# keybaord60.net
KiCad netlist of a schematic drawn in EAGLE
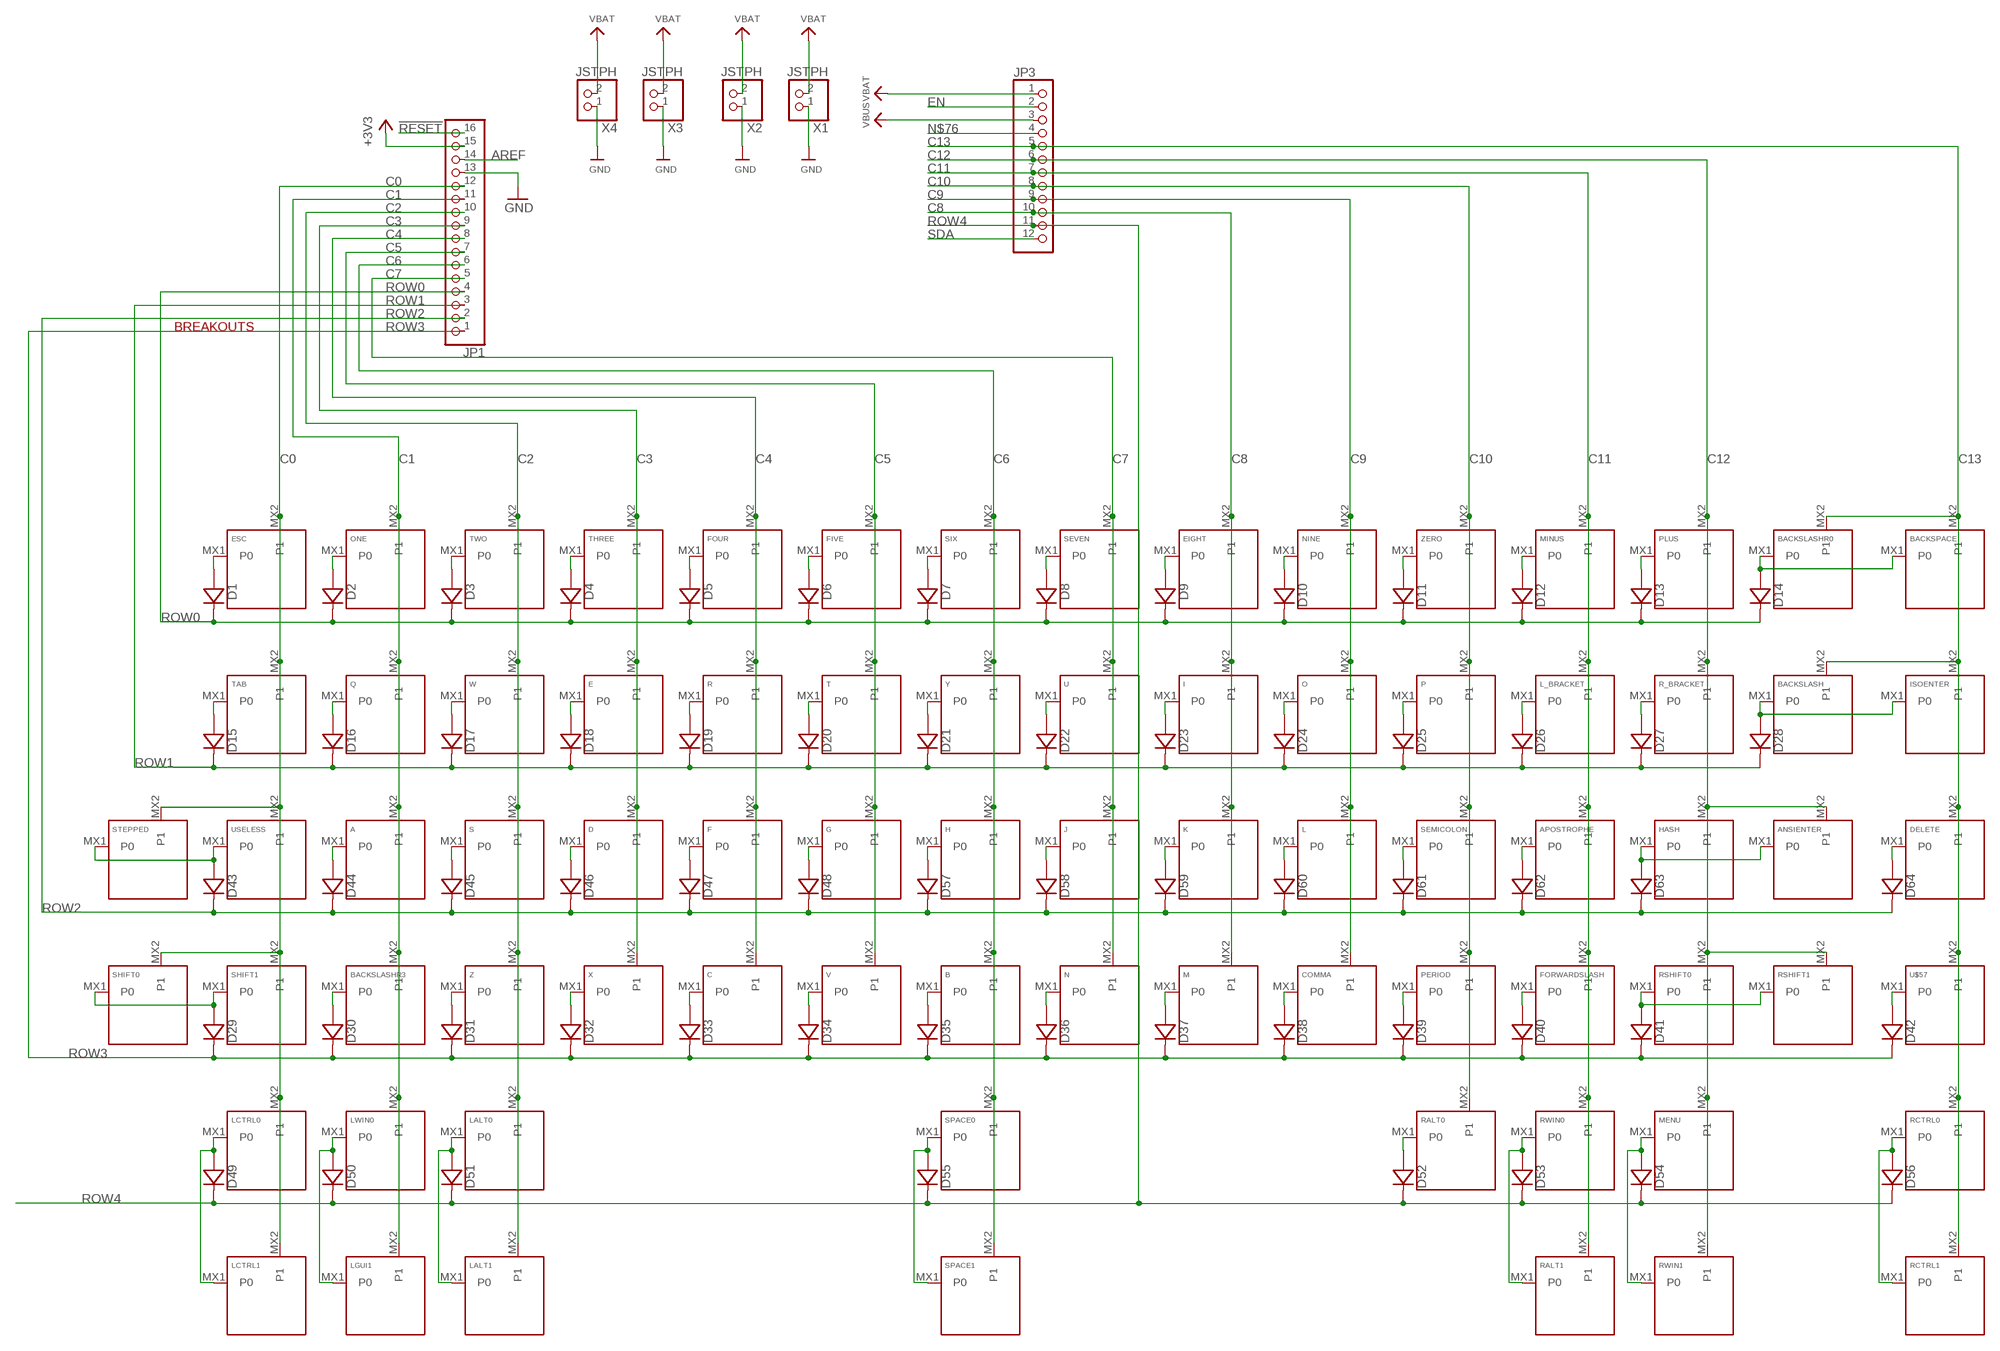
[diagram p0: schematic, sheet 1]

(export (version "E")
  (design (tool "Eeschema 10.0.6"))
  (components
    (comp (ref "A")
      (value "KEYSWITCH-PLAIN-MX-1U")
      (footprint "eagle-import:MX-1U")
      (libsource (lib "eagle-import") (part "KEYSWITCH-PLAIN-MX-1U"))
    )
    (comp (ref "ANSIENTER")
      (value "KEYSWITCH-PLAIN-MX-2U")
      (footprint "eagle-import:MX-2U")
      (libsource (lib "eagle-import") (part "KEYSWITCH-PLAIN-MX-2U"))
    )
    (comp (ref "APOSTROPHE")
      (value "KEYSWITCH-PLAIN-MX-1U")
      (footprint "eagle-import:MX-1U")
      (libsource (lib "eagle-import") (part "KEYSWITCH-PLAIN-MX-1U"))
    )
    (comp (ref "B")
      (value "KEYSWITCH-PLAIN-MX-1U")
      (footprint "eagle-import:MX-1U")
      (libsource (lib "eagle-import") (part "KEYSWITCH-PLAIN-MX-1U"))
    )
    (comp (ref "BACKSLASH")
      (value "KEYSWITCH-PLAIN-MX-1U")
      (footprint "eagle-import:MX-1U")
      (libsource (lib "eagle-import") (part "KEYSWITCH-PLAIN-MX-1U"))
    )
    (comp (ref "BACKSLASHR0")
      (value "KEYSWITCH-PLAIN-MX-1U")
      (footprint "eagle-import:MX-1U")
      (libsource (lib "eagle-import") (part "KEYSWITCH-PLAIN-MX-1U"))
    )
    (comp (ref "BACKSLASHR3")
      (value "KEYSWITCH-PLAIN-MX-1U")
      (footprint "eagle-import:MX-1U")
      (libsource (lib "eagle-import") (part "KEYSWITCH-PLAIN-MX-1U"))
    )
    (comp (ref "BACKSPACE")
      (value "KEYSWITCH-PLAIN-MX-2U")
      (footprint "eagle-import:MX-2U")
      (libsource (lib "eagle-import") (part "KEYSWITCH-PLAIN-MX-2U"))
    )
    (comp (ref "C")
      (value "KEYSWITCH-PLAIN-MX-1U")
      (footprint "eagle-import:MX-1U")
      (libsource (lib "eagle-import") (part "KEYSWITCH-PLAIN-MX-1U"))
    )
    (comp (ref "COMMA")
      (value "KEYSWITCH-PLAIN-MX-1U")
      (footprint "eagle-import:MX-1U")
      (libsource (lib "eagle-import") (part "KEYSWITCH-PLAIN-MX-1U"))
    )
    (comp (ref "D")
      (value "KEYSWITCH-PLAIN-MX-1U")
      (footprint "eagle-import:MX-1U")
      (libsource (lib "eagle-import") (part "KEYSWITCH-PLAIN-MX-1U"))
    )
    (comp (ref "D1")
      (value "DIODE-SOD-123")
      (footprint "eagle-import:SOD-123")
      (libsource (lib "eagle-import") (part "DIODE-SOD-123"))
    )
    (comp (ref "D2")
      (value "DIODE-SOD-123")
      (footprint "eagle-import:SOD-123")
      (libsource (lib "eagle-import") (part "DIODE-SOD-123"))
    )
    (comp (ref "D3")
      (value "DIODE-SOD-123")
      (footprint "eagle-import:SOD-123")
      (libsource (lib "eagle-import") (part "DIODE-SOD-123"))
    )
    (comp (ref "D4")
      (value "DIODE-SOD-123")
      (footprint "eagle-import:SOD-123")
      (libsource (lib "eagle-import") (part "DIODE-SOD-123"))
    )
    (comp (ref "D5")
      (value "DIODE-SOD-123")
      (footprint "eagle-import:SOD-123")
      (libsource (lib "eagle-import") (part "DIODE-SOD-123"))
    )
    (comp (ref "D6")
      (value "DIODE-SOD-123")
      (footprint "eagle-import:SOD-123")
      (libsource (lib "eagle-import") (part "DIODE-SOD-123"))
    )
    (comp (ref "D7")
      (value "DIODE-SOD-123")
      (footprint "eagle-import:SOD-123")
      (libsource (lib "eagle-import") (part "DIODE-SOD-123"))
    )
    (comp (ref "D8")
      (value "DIODE-SOD-123")
      (footprint "eagle-import:SOD-123")
      (libsource (lib "eagle-import") (part "DIODE-SOD-123"))
    )
    (comp (ref "D9")
      (value "DIODE-SOD-123")
      (footprint "eagle-import:SOD-123")
      (libsource (lib "eagle-import") (part "DIODE-SOD-123"))
    )
    (comp (ref "D10")
      (value "DIODE-SOD-123")
      (footprint "eagle-import:SOD-123")
      (libsource (lib "eagle-import") (part "DIODE-SOD-123"))
    )
    (comp (ref "D11")
      (value "DIODE-SOD-123")
      (footprint "eagle-import:SOD-123")
      (libsource (lib "eagle-import") (part "DIODE-SOD-123"))
    )
    (comp (ref "D12")
      (value "DIODE-SOD-123")
      (footprint "eagle-import:SOD-123")
      (libsource (lib "eagle-import") (part "DIODE-SOD-123"))
    )
    (comp (ref "D13")
      (value "DIODE-SOD-123")
      (footprint "eagle-import:SOD-123")
      (libsource (lib "eagle-import") (part "DIODE-SOD-123"))
    )
    (comp (ref "D14")
      (value "DIODE-SOD-123")
      (footprint "eagle-import:SOD-123")
      (libsource (lib "eagle-import") (part "DIODE-SOD-123"))
    )
    (comp (ref "D15")
      (value "DIODE-SOD-123")
      (footprint "eagle-import:SOD-123")
      (libsource (lib "eagle-import") (part "DIODE-SOD-123"))
    )
    (comp (ref "D16")
      (value "DIODE-SOD-123")
      (footprint "eagle-import:SOD-123")
      (libsource (lib "eagle-import") (part "DIODE-SOD-123"))
    )
    (comp (ref "D17")
      (value "DIODE-SOD-123")
      (footprint "eagle-import:SOD-123")
      (libsource (lib "eagle-import") (part "DIODE-SOD-123"))
    )
    (comp (ref "D18")
      (value "DIODE-SOD-123")
      (footprint "eagle-import:SOD-123")
      (libsource (lib "eagle-import") (part "DIODE-SOD-123"))
    )
    (comp (ref "D19")
      (value "DIODE-SOD-123")
      (footprint "eagle-import:SOD-123")
      (libsource (lib "eagle-import") (part "DIODE-SOD-123"))
    )
    (comp (ref "D20")
      (value "DIODE-SOD-123")
      (footprint "eagle-import:SOD-123")
      (libsource (lib "eagle-import") (part "DIODE-SOD-123"))
    )
    (comp (ref "D21")
      (value "DIODE-SOD-123")
      (footprint "eagle-import:SOD-123")
      (libsource (lib "eagle-import") (part "DIODE-SOD-123"))
    )
    (comp (ref "D22")
      (value "DIODE-SOD-123")
      (footprint "eagle-import:SOD-123")
      (libsource (lib "eagle-import") (part "DIODE-SOD-123"))
    )
    (comp (ref "D23")
      (value "DIODE-SOD-123")
      (footprint "eagle-import:SOD-123")
      (libsource (lib "eagle-import") (part "DIODE-SOD-123"))
    )
    (comp (ref "D24")
      (value "DIODE-SOD-123")
      (footprint "eagle-import:SOD-123")
      (libsource (lib "eagle-import") (part "DIODE-SOD-123"))
    )
    (comp (ref "D25")
      (value "DIODE-SOD-123")
      (footprint "eagle-import:SOD-123")
      (libsource (lib "eagle-import") (part "DIODE-SOD-123"))
    )
    (comp (ref "D26")
      (value "DIODE-SOD-123")
      (footprint "eagle-import:SOD-123")
      (libsource (lib "eagle-import") (part "DIODE-SOD-123"))
    )
    (comp (ref "D27")
      (value "DIODE-SOD-123")
      (footprint "eagle-import:SOD-123")
      (libsource (lib "eagle-import") (part "DIODE-SOD-123"))
    )
    (comp (ref "D28")
      (value "DIODE-SOD-123")
      (footprint "eagle-import:SOD-123")
      (libsource (lib "eagle-import") (part "DIODE-SOD-123"))
    )
    (comp (ref "D29")
      (value "DIODE-SOD-123")
      (footprint "eagle-import:SOD-123")
      (libsource (lib "eagle-import") (part "DIODE-SOD-123"))
    )
    (comp (ref "D30")
      (value "DIODE-SOD-123")
      (footprint "eagle-import:SOD-123")
      (libsource (lib "eagle-import") (part "DIODE-SOD-123"))
    )
    (comp (ref "D31")
      (value "DIODE-SOD-123")
      (footprint "eagle-import:SOD-123")
      (libsource (lib "eagle-import") (part "DIODE-SOD-123"))
    )
    (comp (ref "D32")
      (value "DIODE-SOD-123")
      (footprint "eagle-import:SOD-123")
      (libsource (lib "eagle-import") (part "DIODE-SOD-123"))
    )
    (comp (ref "D33")
      (value "DIODE-SOD-123")
      (footprint "eagle-import:SOD-123")
      (libsource (lib "eagle-import") (part "DIODE-SOD-123"))
    )
    (comp (ref "D34")
      (value "DIODE-SOD-123")
      (footprint "eagle-import:SOD-123")
      (libsource (lib "eagle-import") (part "DIODE-SOD-123"))
    )
    (comp (ref "D35")
      (value "DIODE-SOD-123")
      (footprint "eagle-import:SOD-123")
      (libsource (lib "eagle-import") (part "DIODE-SOD-123"))
    )
    (comp (ref "D36")
      (value "DIODE-SOD-123")
      (footprint "eagle-import:SOD-123")
      (libsource (lib "eagle-import") (part "DIODE-SOD-123"))
    )
    (comp (ref "D37")
      (value "DIODE-SOD-123")
      (footprint "eagle-import:SOD-123")
      (libsource (lib "eagle-import") (part "DIODE-SOD-123"))
    )
    (comp (ref "D38")
      (value "DIODE-SOD-123")
      (footprint "eagle-import:SOD-123")
      (libsource (lib "eagle-import") (part "DIODE-SOD-123"))
    )
    (comp (ref "D39")
      (value "DIODE-SOD-123")
      (footprint "eagle-import:SOD-123")
      (libsource (lib "eagle-import") (part "DIODE-SOD-123"))
    )
    (comp (ref "D40")
      (value "DIODE-SOD-123")
      (footprint "eagle-import:SOD-123")
      (libsource (lib "eagle-import") (part "DIODE-SOD-123"))
    )
    (comp (ref "D41")
      (value "DIODE-SOD-123")
      (footprint "eagle-import:SOD-123")
      (libsource (lib "eagle-import") (part "DIODE-SOD-123"))
    )
    (comp (ref "D42")
      (value "DIODE-SOD-123")
      (footprint "eagle-import:SOD-123")
      (libsource (lib "eagle-import") (part "DIODE-SOD-123"))
    )
    (comp (ref "D43")
      (value "DIODE-SOD-123")
      (footprint "eagle-import:SOD-123")
      (libsource (lib "eagle-import") (part "DIODE-SOD-123"))
    )
    (comp (ref "D44")
      (value "DIODE-SOD-123")
      (footprint "eagle-import:SOD-123")
      (libsource (lib "eagle-import") (part "DIODE-SOD-123"))
    )
    (comp (ref "D45")
      (value "DIODE-SOD-123")
      (footprint "eagle-import:SOD-123")
      (libsource (lib "eagle-import") (part "DIODE-SOD-123"))
    )
    (comp (ref "D46")
      (value "DIODE-SOD-123")
      (footprint "eagle-import:SOD-123")
      (libsource (lib "eagle-import") (part "DIODE-SOD-123"))
    )
    (comp (ref "D47")
      (value "DIODE-SOD-123")
      (footprint "eagle-import:SOD-123")
      (libsource (lib "eagle-import") (part "DIODE-SOD-123"))
    )
    (comp (ref "D48")
      (value "DIODE-SOD-123")
      (footprint "eagle-import:SOD-123")
      (libsource (lib "eagle-import") (part "DIODE-SOD-123"))
    )
    (comp (ref "D49")
      (value "DIODE-SOD-123")
      (footprint "eagle-import:SOD-123")
      (libsource (lib "eagle-import") (part "DIODE-SOD-123"))
    )
    (comp (ref "D50")
      (value "DIODE-SOD-123")
      (footprint "eagle-import:SOD-123")
      (libsource (lib "eagle-import") (part "DIODE-SOD-123"))
    )
    (comp (ref "D51")
      (value "DIODE-SOD-123")
      (footprint "eagle-import:SOD-123")
      (libsource (lib "eagle-import") (part "DIODE-SOD-123"))
    )
    (comp (ref "D52")
      (value "DIODE-SOD-123")
      (footprint "eagle-import:SOD-123")
      (libsource (lib "eagle-import") (part "DIODE-SOD-123"))
    )
    (comp (ref "D53")
      (value "DIODE-SOD-123")
      (footprint "eagle-import:SOD-123")
      (libsource (lib "eagle-import") (part "DIODE-SOD-123"))
    )
    (comp (ref "D54")
      (value "DIODE-SOD-123")
      (footprint "eagle-import:SOD-123")
      (libsource (lib "eagle-import") (part "DIODE-SOD-123"))
    )
    (comp (ref "D55")
      (value "DIODE-SOD-123")
      (footprint "eagle-import:SOD-123")
      (libsource (lib "eagle-import") (part "DIODE-SOD-123"))
    )
    (comp (ref "D56")
      (value "DIODE-SOD-123")
      (footprint "eagle-import:SOD-123")
      (libsource (lib "eagle-import") (part "DIODE-SOD-123"))
    )
    (comp (ref "D57")
      (value "DIODE-SOD-123")
      (footprint "eagle-import:SOD-123")
      (libsource (lib "eagle-import") (part "DIODE-SOD-123"))
    )
    (comp (ref "D58")
      (value "DIODE-SOD-123")
      (footprint "eagle-import:SOD-123")
      (libsource (lib "eagle-import") (part "DIODE-SOD-123"))
    )
    (comp (ref "D59")
      (value "DIODE-SOD-123")
      (footprint "eagle-import:SOD-123")
      (libsource (lib "eagle-import") (part "DIODE-SOD-123"))
    )
    (comp (ref "D60")
      (value "DIODE-SOD-123")
      (footprint "eagle-import:SOD-123")
      (libsource (lib "eagle-import") (part "DIODE-SOD-123"))
    )
    (comp (ref "D61")
      (value "DIODE-SOD-123")
      (footprint "eagle-import:SOD-123")
      (libsource (lib "eagle-import") (part "DIODE-SOD-123"))
    )
    (comp (ref "D62")
      (value "DIODE-SOD-123")
      (footprint "eagle-import:SOD-123")
      (libsource (lib "eagle-import") (part "DIODE-SOD-123"))
    )
    (comp (ref "D63")
      (value "DIODE-SOD-123")
      (footprint "eagle-import:SOD-123")
      (libsource (lib "eagle-import") (part "DIODE-SOD-123"))
    )
    (comp (ref "D64")
      (value "DIODE-SOD-123")
      (footprint "eagle-import:SOD-123")
      (libsource (lib "eagle-import") (part "DIODE-SOD-123"))
    )
    (comp (ref "DELETE")
      (value "KEYSWITCH-PLAIN-MX-1U")
      (footprint "eagle-import:MX-1U")
      (libsource (lib "eagle-import") (part "KEYSWITCH-PLAIN-MX-1U"))
    )
    (comp (ref "E")
      (value "KEYSWITCH-PLAIN-MX-1U")
      (footprint "eagle-import:MX-1U")
      (libsource (lib "eagle-import") (part "KEYSWITCH-PLAIN-MX-1U"))
    )
    (comp (ref "EIGHT")
      (value "KEYSWITCH-PLAIN-MX-1U")
      (footprint "eagle-import:MX-1U")
      (libsource (lib "eagle-import") (part "KEYSWITCH-PLAIN-MX-1U"))
    )
    (comp (ref "ESC")
      (value "KEYSWITCH-PLAIN-MX-1U")
      (footprint "eagle-import:MX-1U")
      (libsource (lib "eagle-import") (part "KEYSWITCH-PLAIN-MX-1U"))
    )
    (comp (ref "F")
      (value "KEYSWITCH-PLAIN-MX-1U")
      (footprint "eagle-import:MX-1U")
      (libsource (lib "eagle-import") (part "KEYSWITCH-PLAIN-MX-1U"))
    )
    (comp (ref "FIVE")
      (value "KEYSWITCH-PLAIN-MX-1U")
      (footprint "eagle-import:MX-1U")
      (libsource (lib "eagle-import") (part "KEYSWITCH-PLAIN-MX-1U"))
    )
    (comp (ref "FORWARDSLASH")
      (value "KEYSWITCH-PLAIN-MX-1U")
      (footprint "eagle-import:MX-1U")
      (libsource (lib "eagle-import") (part "KEYSWITCH-PLAIN-MX-1U"))
    )
    (comp (ref "FOUR")
      (value "KEYSWITCH-PLAIN-MX-1U")
      (footprint "eagle-import:MX-1U")
      (libsource (lib "eagle-import") (part "KEYSWITCH-PLAIN-MX-1U"))
    )
    (comp (ref "G")
      (value "KEYSWITCH-PLAIN-MX-1U")
      (footprint "eagle-import:MX-1U")
      (libsource (lib "eagle-import") (part "KEYSWITCH-PLAIN-MX-1U"))
    )
    (comp (ref "H")
      (value "KEYSWITCH-PLAIN-MX-1U")
      (footprint "eagle-import:MX-1U")
      (libsource (lib "eagle-import") (part "KEYSWITCH-PLAIN-MX-1U"))
    )
    (comp (ref "HASH")
      (value "KEYSWITCH-PLAIN-MX-1U")
      (footprint "eagle-import:MX-1U")
      (libsource (lib "eagle-import") (part "KEYSWITCH-PLAIN-MX-1U"))
    )
    (comp (ref "I")
      (value "KEYSWITCH-PLAIN-MX-1U")
      (footprint "eagle-import:MX-1U")
      (libsource (lib "eagle-import") (part "KEYSWITCH-PLAIN-MX-1U"))
    )
    (comp (ref "ISOENTER")
      (value "KEYSWITCH-PLAIN-MX-2U-ROTATED")
      (footprint "eagle-import:MX-2U-ROTATED")
      (libsource (lib "eagle-import") (part "KEYSWITCH-PLAIN-MX-2U-ROTATED"))
    )
    (comp (ref "J")
      (value "KEYSWITCH-PLAIN-MX-1U")
      (footprint "eagle-import:MX-1U")
      (libsource (lib "eagle-import") (part "KEYSWITCH-PLAIN-MX-1U"))
    )
    (comp (ref "JP1")
      (value "HEADER-1X16ROUND")
      (footprint "eagle-import:1X16_ROUND")
      (libsource (lib "eagle-import") (part "HEADER-1X16ROUND"))
    )
    (comp (ref "JP3")
      (value "HEADER-1X12")
      (footprint "eagle-import:1X12_ROUND")
      (libsource (lib "eagle-import") (part "HEADER-1X12"))
    )
    (comp (ref "K")
      (value "KEYSWITCH-PLAIN-MX-1U")
      (footprint "eagle-import:MX-1U")
      (libsource (lib "eagle-import") (part "KEYSWITCH-PLAIN-MX-1U"))
    )
    (comp (ref "L")
      (value "KEYSWITCH-PLAIN-MX-1U")
      (footprint "eagle-import:MX-1U")
      (libsource (lib "eagle-import") (part "KEYSWITCH-PLAIN-MX-1U"))
    )
    (comp (ref "LALT0")
      (value "KEYSWITCH-PLAIN-MX-1U")
      (footprint "eagle-import:MX-1U")
      (libsource (lib "eagle-import") (part "KEYSWITCH-PLAIN-MX-1U"))
    )
    (comp (ref "LALT1")
      (value "KEYSWITCH-PLAIN-MX-1U")
      (footprint "eagle-import:MX-1U")
      (libsource (lib "eagle-import") (part "KEYSWITCH-PLAIN-MX-1U"))
    )
    (comp (ref "LCTRL0")
      (value "KEYSWITCH-PLAIN-MX-1U")
      (footprint "eagle-import:MX-1U")
      (libsource (lib "eagle-import") (part "KEYSWITCH-PLAIN-MX-1U"))
    )
    (comp (ref "LCTRL1")
      (value "KEYSWITCH-PLAIN-MX-1U")
      (footprint "eagle-import:MX-1U")
      (libsource (lib "eagle-import") (part "KEYSWITCH-PLAIN-MX-1U"))
    )
    (comp (ref "LGUI1")
      (value "KEYSWITCH-PLAIN-MX-1U")
      (footprint "eagle-import:MX-1U")
      (libsource (lib "eagle-import") (part "KEYSWITCH-PLAIN-MX-1U"))
    )
    (comp (ref "LWIN0")
      (value "KEYSWITCH-PLAIN-MX-1U")
      (footprint "eagle-import:MX-1U")
      (libsource (lib "eagle-import") (part "KEYSWITCH-PLAIN-MX-1U"))
    )
    (comp (ref "L_BRACKET")
      (value "KEYSWITCH-PLAIN-MX-1U")
      (footprint "eagle-import:MX-1U")
      (libsource (lib "eagle-import") (part "KEYSWITCH-PLAIN-MX-1U"))
    )
    (comp (ref "M")
      (value "KEYSWITCH-PLAIN-MX-1U")
      (footprint "eagle-import:MX-1U")
      (libsource (lib "eagle-import") (part "KEYSWITCH-PLAIN-MX-1U"))
    )
    (comp (ref "MENU")
      (value "KEYSWITCH-PLAIN-MX-1U")
      (footprint "eagle-import:MX-1U")
      (libsource (lib "eagle-import") (part "KEYSWITCH-PLAIN-MX-1U"))
    )
    (comp (ref "MINUS")
      (value "KEYSWITCH-PLAIN-MX-1U")
      (footprint "eagle-import:MX-1U")
      (libsource (lib "eagle-import") (part "KEYSWITCH-PLAIN-MX-1U"))
    )
    (comp (ref "N")
      (value "KEYSWITCH-PLAIN-MX-1U")
      (footprint "eagle-import:MX-1U")
      (libsource (lib "eagle-import") (part "KEYSWITCH-PLAIN-MX-1U"))
    )
    (comp (ref "NINE")
      (value "KEYSWITCH-PLAIN-MX-1U")
      (footprint "eagle-import:MX-1U")
      (libsource (lib "eagle-import") (part "KEYSWITCH-PLAIN-MX-1U"))
    )
    (comp (ref "O")
      (value "KEYSWITCH-PLAIN-MX-1U")
      (footprint "eagle-import:MX-1U")
      (libsource (lib "eagle-import") (part "KEYSWITCH-PLAIN-MX-1U"))
    )
    (comp (ref "ONE")
      (value "KEYSWITCH-PLAIN-MX-1U")
      (footprint "eagle-import:MX-1U")
      (libsource (lib "eagle-import") (part "KEYSWITCH-PLAIN-MX-1U"))
    )
    (comp (ref "P")
      (value "KEYSWITCH-PLAIN-MX-1U")
      (footprint "eagle-import:MX-1U")
      (libsource (lib "eagle-import") (part "KEYSWITCH-PLAIN-MX-1U"))
    )
    (comp (ref "PERIOD")
      (value "KEYSWITCH-PLAIN-MX-1U")
      (footprint "eagle-import:MX-1U")
      (libsource (lib "eagle-import") (part "KEYSWITCH-PLAIN-MX-1U"))
    )
    (comp (ref "PLUS")
      (value "KEYSWITCH-PLAIN-MX-1U")
      (footprint "eagle-import:MX-1U")
      (libsource (lib "eagle-import") (part "KEYSWITCH-PLAIN-MX-1U"))
    )
    (comp (ref "Q")
      (value "KEYSWITCH-PLAIN-MX-1U")
      (footprint "eagle-import:MX-1U")
      (libsource (lib "eagle-import") (part "KEYSWITCH-PLAIN-MX-1U"))
    )
    (comp (ref "R")
      (value "KEYSWITCH-PLAIN-MX-1U")
      (footprint "eagle-import:MX-1U")
      (libsource (lib "eagle-import") (part "KEYSWITCH-PLAIN-MX-1U"))
    )
    (comp (ref "RALT0")
      (value "KEYSWITCH-PLAIN-MX-1U")
      (footprint "eagle-import:MX-1U")
      (libsource (lib "eagle-import") (part "KEYSWITCH-PLAIN-MX-1U"))
    )
    (comp (ref "RALT1")
      (value "KEYSWITCH-PLAIN-MX-1U")
      (footprint "eagle-import:MX-1U")
      (libsource (lib "eagle-import") (part "KEYSWITCH-PLAIN-MX-1U"))
    )
    (comp (ref "RCTRL0")
      (value "KEYSWITCH-PLAIN-MX-1U")
      (footprint "eagle-import:MX-1U")
      (libsource (lib "eagle-import") (part "KEYSWITCH-PLAIN-MX-1U"))
    )
    (comp (ref "RCTRL1")
      (value "KEYSWITCH-PLAIN-MX-1U")
      (footprint "eagle-import:MX-1U")
      (libsource (lib "eagle-import") (part "KEYSWITCH-PLAIN-MX-1U"))
    )
    (comp (ref "RSHIFT0")
      (value "KEYSWITCH-PLAIN-MX-1U")
      (footprint "eagle-import:MX-1U")
      (libsource (lib "eagle-import") (part "KEYSWITCH-PLAIN-MX-1U"))
    )
    (comp (ref "RSHIFT1")
      (value "KEYSWITCH-PLAIN-MX-2U")
      (footprint "eagle-import:MX-2U")
      (libsource (lib "eagle-import") (part "KEYSWITCH-PLAIN-MX-2U"))
    )
    (comp (ref "RWIN0")
      (value "KEYSWITCH-PLAIN-MX-1U")
      (footprint "eagle-import:MX-1U")
      (libsource (lib "eagle-import") (part "KEYSWITCH-PLAIN-MX-1U"))
    )
    (comp (ref "RWIN1")
      (value "KEYSWITCH-PLAIN-MX-1U")
      (footprint "eagle-import:MX-1U")
      (libsource (lib "eagle-import") (part "KEYSWITCH-PLAIN-MX-1U"))
    )
    (comp (ref "R_BRACKET")
      (value "KEYSWITCH-PLAIN-MX-1U")
      (footprint "eagle-import:MX-1U")
      (libsource (lib "eagle-import") (part "KEYSWITCH-PLAIN-MX-1U"))
    )
    (comp (ref "S")
      (value "KEYSWITCH-PLAIN-MX-1U")
      (footprint "eagle-import:MX-1U")
      (libsource (lib "eagle-import") (part "KEYSWITCH-PLAIN-MX-1U"))
    )
    (comp (ref "SEMICOLON")
      (value "KEYSWITCH-PLAIN-MX-1U")
      (footprint "eagle-import:MX-1U")
      (libsource (lib "eagle-import") (part "KEYSWITCH-PLAIN-MX-1U"))
    )
    (comp (ref "SEVEN")
      (value "KEYSWITCH-PLAIN-MX-1U")
      (footprint "eagle-import:MX-1U")
      (libsource (lib "eagle-import") (part "KEYSWITCH-PLAIN-MX-1U"))
    )
    (comp (ref "SHIFT0")
      (value "KEYSWITCH-PLAIN-MX-1U")
      (footprint "eagle-import:MX-1U")
      (libsource (lib "eagle-import") (part "KEYSWITCH-PLAIN-MX-1U"))
    )
    (comp (ref "SHIFT1")
      (value "KEYSWITCH-PLAIN-MX-2U")
      (footprint "eagle-import:MX-2U")
      (libsource (lib "eagle-import") (part "KEYSWITCH-PLAIN-MX-2U"))
    )
    (comp (ref "SIX")
      (value "KEYSWITCH-PLAIN-MX-1U")
      (footprint "eagle-import:MX-1U")
      (libsource (lib "eagle-import") (part "KEYSWITCH-PLAIN-MX-1U"))
    )
    (comp (ref "SPACE0")
      (value "KEYSWITCH-PLAIN-MX-6.25U-FLIPPED")
      (footprint "eagle-import:MX-6.25U-FLIPPED")
      (libsource (lib "eagle-import") (part "KEYSWITCH-PLAIN-MX-6.25U-FLIPPED"))
    )
    (comp (ref "SPACE1")
      (value "KEYSWITCH-PLAIN-MX-7U-FLIPPED")
      (footprint "eagle-import:MX-7U-FLIPPED")
      (libsource (lib "eagle-import") (part "KEYSWITCH-PLAIN-MX-7U-FLIPPED"))
    )
    (comp (ref "STEPPED")
      (value "KEYSWITCH-PLAIN-MX-1U")
      (footprint "eagle-import:MX-1U")
      (libsource (lib "eagle-import") (part "KEYSWITCH-PLAIN-MX-1U"))
    )
    (comp (ref "T")
      (value "KEYSWITCH-PLAIN-MX-1U")
      (footprint "eagle-import:MX-1U")
      (libsource (lib "eagle-import") (part "KEYSWITCH-PLAIN-MX-1U"))
    )
    (comp (ref "TAB")
      (value "KEYSWITCH-PLAIN-MX-1U")
      (footprint "eagle-import:MX-1U")
      (libsource (lib "eagle-import") (part "KEYSWITCH-PLAIN-MX-1U"))
    )
    (comp (ref "THREE")
      (value "KEYSWITCH-PLAIN-MX-1U")
      (footprint "eagle-import:MX-1U")
      (libsource (lib "eagle-import") (part "KEYSWITCH-PLAIN-MX-1U"))
    )
    (comp (ref "TWO")
      (value "KEYSWITCH-PLAIN-MX-1U")
      (footprint "eagle-import:MX-1U")
      (libsource (lib "eagle-import") (part "KEYSWITCH-PLAIN-MX-1U"))
    )
    (comp (ref "U")
      (value "KEYSWITCH-PLAIN-MX-1U")
      (footprint "eagle-import:MX-1U")
      (libsource (lib "eagle-import") (part "KEYSWITCH-PLAIN-MX-1U"))
    )
    (comp (ref "U$57")
      (value "KEYSWITCH-PLAIN-MX-1U")
      (footprint "eagle-import:MX-1U")
      (libsource (lib "eagle-import") (part "KEYSWITCH-PLAIN-MX-1U"))
    )
    (comp (ref "USELESS")
      (value "KEYSWITCH-PLAIN-MX-1U")
      (footprint "eagle-import:MX-1U")
      (libsource (lib "eagle-import") (part "KEYSWITCH-PLAIN-MX-1U"))
    )
    (comp (ref "V")
      (value "KEYSWITCH-PLAIN-MX-1U")
      (footprint "eagle-import:MX-1U")
      (libsource (lib "eagle-import") (part "KEYSWITCH-PLAIN-MX-1U"))
    )
    (comp (ref "W")
      (value "KEYSWITCH-PLAIN-MX-1U")
      (footprint "eagle-import:MX-1U")
      (libsource (lib "eagle-import") (part "KEYSWITCH-PLAIN-MX-1U"))
    )
    (comp (ref "X")
      (value "KEYSWITCH-PLAIN-MX-1U")
      (footprint "eagle-import:MX-1U")
      (libsource (lib "eagle-import") (part "KEYSWITCH-PLAIN-MX-1U"))
    )
    (comp (ref "X1")
      (value "JSTPH")
      (footprint "eagle-import:JSTPH2")
      (libsource (lib "eagle-import") (part "CON_JST_PH_2PIN"))
    )
    (comp (ref "X2")
      (value "JSTPH")
      (footprint "eagle-import:JSTPH2")
      (libsource (lib "eagle-import") (part "CON_JST_PH_2PIN"))
    )
    (comp (ref "X3")
      (value "JSTPH")
      (footprint "eagle-import:JSTPH2")
      (libsource (lib "eagle-import") (part "CON_JST_PH_2PIN"))
    )
    (comp (ref "X4")
      (value "JSTPH")
      (footprint "eagle-import:JSTPH2")
      (libsource (lib "eagle-import") (part "CON_JST_PH_2PIN"))
    )
    (comp (ref "Y")
      (value "KEYSWITCH-PLAIN-MX-1U")
      (footprint "eagle-import:MX-1U")
      (libsource (lib "eagle-import") (part "KEYSWITCH-PLAIN-MX-1U"))
    )
    (comp (ref "Z")
      (value "KEYSWITCH-PLAIN-MX-1U")
      (footprint "eagle-import:MX-1U")
      (libsource (lib "eagle-import") (part "KEYSWITCH-PLAIN-MX-1U"))
    )
    (comp (ref "ZERO")
      (value "KEYSWITCH-PLAIN-MX-1U")
      (footprint "eagle-import:MX-1U")
      (libsource (lib "eagle-import") (part "KEYSWITCH-PLAIN-MX-1U"))
    )
  )
  (nets
    (net (code "1") (name "+3V3") (class "Default")
      (node (ref "JP1") (pin "15") (pinfunction "15_15") (pintype "passive"))
    )
    (net (code "2") (name "/AREF") (class "Default")
      (node (ref "JP1") (pin "14") (pinfunction "14_14") (pintype "passive"))
    )
    (net (code "3") (name "/C0") (class "Default")
      (node (ref "ESC") (pin "MX2") (pinfunction "P1_MX2") (pintype "bidirectional"))
      (node (ref "JP1") (pin "12") (pinfunction "12_12") (pintype "passive"))
      (node (ref "LCTRL0") (pin "MX2") (pinfunction "P1_MX2") (pintype "bidirectional"))
      (node (ref "LCTRL1") (pin "MX2") (pinfunction "P1_MX2") (pintype "bidirectional"))
      (node (ref "SHIFT0") (pin "MX2") (pinfunction "P1_MX2") (pintype "bidirectional"))
      (node (ref "SHIFT1") (pin "MX2") (pinfunction "P1_MX2") (pintype "bidirectional"))
      (node (ref "STEPPED") (pin "MX2") (pinfunction "P1_MX2") (pintype "bidirectional"))
      (node (ref "TAB") (pin "MX2") (pinfunction "P1_MX2") (pintype "bidirectional"))
      (node (ref "USELESS") (pin "MX2") (pinfunction "P1_MX2") (pintype "bidirectional"))
    )
    (net (code "4") (name "/C1") (class "Default")
      (node (ref "A") (pin "MX2") (pinfunction "P1_MX2") (pintype "bidirectional"))
      (node (ref "BACKSLASHR3") (pin "MX2") (pinfunction "P1_MX2") (pintype "bidirectional"))
      (node (ref "JP1") (pin "11") (pinfunction "11_11") (pintype "passive"))
      (node (ref "LGUI1") (pin "MX2") (pinfunction "P1_MX2") (pintype "bidirectional"))
      (node (ref "LWIN0") (pin "MX2") (pinfunction "P1_MX2") (pintype "bidirectional"))
      (node (ref "ONE") (pin "MX2") (pinfunction "P1_MX2") (pintype "bidirectional"))
      (node (ref "Q") (pin "MX2") (pinfunction "P1_MX2") (pintype "bidirectional"))
    )
    (net (code "5") (name "/C2") (class "Default")
      (node (ref "JP1") (pin "10") (pinfunction "10_10") (pintype "passive"))
      (node (ref "LALT0") (pin "MX2") (pinfunction "P1_MX2") (pintype "bidirectional"))
      (node (ref "LALT1") (pin "MX2") (pinfunction "P1_MX2") (pintype "bidirectional"))
      (node (ref "S") (pin "MX2") (pinfunction "P1_MX2") (pintype "bidirectional"))
      (node (ref "TWO") (pin "MX2") (pinfunction "P1_MX2") (pintype "bidirectional"))
      (node (ref "W") (pin "MX2") (pinfunction "P1_MX2") (pintype "bidirectional"))
      (node (ref "Z") (pin "MX2") (pinfunction "P1_MX2") (pintype "bidirectional"))
    )
    (net (code "6") (name "/C3") (class "Default")
      (node (ref "D") (pin "MX2") (pinfunction "P1_MX2") (pintype "bidirectional"))
      (node (ref "E") (pin "MX2") (pinfunction "P1_MX2") (pintype "bidirectional"))
      (node (ref "JP1") (pin "9") (pinfunction "9_9") (pintype "passive"))
      (node (ref "THREE") (pin "MX2") (pinfunction "P1_MX2") (pintype "bidirectional"))
      (node (ref "X") (pin "MX2") (pinfunction "P1_MX2") (pintype "bidirectional"))
    )
    (net (code "7") (name "/C4") (class "Default")
      (node (ref "C") (pin "MX2") (pinfunction "P1_MX2") (pintype "bidirectional"))
      (node (ref "F") (pin "MX2") (pinfunction "P1_MX2") (pintype "bidirectional"))
      (node (ref "FOUR") (pin "MX2") (pinfunction "P1_MX2") (pintype "bidirectional"))
      (node (ref "JP1") (pin "8") (pinfunction "8_8") (pintype "passive"))
      (node (ref "R") (pin "MX2") (pinfunction "P1_MX2") (pintype "bidirectional"))
    )
    (net (code "8") (name "/C5") (class "Default")
      (node (ref "FIVE") (pin "MX2") (pinfunction "P1_MX2") (pintype "bidirectional"))
      (node (ref "G") (pin "MX2") (pinfunction "P1_MX2") (pintype "bidirectional"))
      (node (ref "JP1") (pin "7") (pinfunction "7_7") (pintype "passive"))
      (node (ref "T") (pin "MX2") (pinfunction "P1_MX2") (pintype "bidirectional"))
      (node (ref "V") (pin "MX2") (pinfunction "P1_MX2") (pintype "bidirectional"))
    )
    (net (code "9") (name "/C6") (class "Default")
      (node (ref "B") (pin "MX2") (pinfunction "P1_MX2") (pintype "bidirectional"))
      (node (ref "H") (pin "MX2") (pinfunction "P1_MX2") (pintype "bidirectional"))
      (node (ref "JP1") (pin "6") (pinfunction "6_6") (pintype "passive"))
      (node (ref "SIX") (pin "MX2") (pinfunction "P1_MX2") (pintype "bidirectional"))
      (node (ref "SPACE0") (pin "MX2") (pinfunction "P1_MX2") (pintype "bidirectional"))
      (node (ref "SPACE1") (pin "MX2") (pinfunction "P1_MX2") (pintype "bidirectional"))
      (node (ref "Y") (pin "MX2") (pinfunction "P1_MX2") (pintype "bidirectional"))
    )
    (net (code "10") (name "/C7") (class "Default")
      (node (ref "J") (pin "MX2") (pinfunction "P1_MX2") (pintype "bidirectional"))
      (node (ref "JP1") (pin "5") (pinfunction "5_5") (pintype "passive"))
      (node (ref "N") (pin "MX2") (pinfunction "P1_MX2") (pintype "bidirectional"))
      (node (ref "SEVEN") (pin "MX2") (pinfunction "P1_MX2") (pintype "bidirectional"))
      (node (ref "U") (pin "MX2") (pinfunction "P1_MX2") (pintype "bidirectional"))
    )
    (net (code "11") (name "/C8") (class "Default")
      (node (ref "EIGHT") (pin "MX2") (pinfunction "P1_MX2") (pintype "bidirectional"))
      (node (ref "I") (pin "MX2") (pinfunction "P1_MX2") (pintype "bidirectional"))
      (node (ref "JP3") (pin "10") (pinfunction "10_10") (pintype "passive"))
      (node (ref "K") (pin "MX2") (pinfunction "P1_MX2") (pintype "bidirectional"))
      (node (ref "M") (pin "MX2") (pinfunction "P1_MX2") (pintype "bidirectional"))
    )
    (net (code "12") (name "/C9") (class "Default")
      (node (ref "COMMA") (pin "MX2") (pinfunction "P1_MX2") (pintype "bidirectional"))
      (node (ref "JP3") (pin "9") (pinfunction "9_9") (pintype "passive"))
      (node (ref "L") (pin "MX2") (pinfunction "P1_MX2") (pintype "bidirectional"))
      (node (ref "NINE") (pin "MX2") (pinfunction "P1_MX2") (pintype "bidirectional"))
      (node (ref "O") (pin "MX2") (pinfunction "P1_MX2") (pintype "bidirectional"))
    )
    (net (code "13") (name "/C10") (class "Default")
      (node (ref "JP3") (pin "8") (pinfunction "8_8") (pintype "passive"))
      (node (ref "P") (pin "MX2") (pinfunction "P1_MX2") (pintype "bidirectional"))
      (node (ref "PERIOD") (pin "MX2") (pinfunction "P1_MX2") (pintype "bidirectional"))
      (node (ref "RALT0") (pin "MX2") (pinfunction "P1_MX2") (pintype "bidirectional"))
      (node (ref "SEMICOLON") (pin "MX2") (pinfunction "P1_MX2") (pintype "bidirectional"))
      (node (ref "ZERO") (pin "MX2") (pinfunction "P1_MX2") (pintype "bidirectional"))
    )
    (net (code "14") (name "/C11") (class "Default")
      (node (ref "APOSTROPHE") (pin "MX2") (pinfunction "P1_MX2") (pintype "bidirectional"))
      (node (ref "FORWARDSLASH") (pin "MX2") (pinfunction "P1_MX2") (pintype "bidirectional"))
      (node (ref "JP3") (pin "7") (pinfunction "7_7") (pintype "passive"))
      (node (ref "L_BRACKET") (pin "MX2") (pinfunction "P1_MX2") (pintype "bidirectional"))
      (node (ref "MINUS") (pin "MX2") (pinfunction "P1_MX2") (pintype "bidirectional"))
      (node (ref "RALT1") (pin "MX2") (pinfunction "P1_MX2") (pintype "bidirectional"))
      (node (ref "RWIN0") (pin "MX2") (pinfunction "P1_MX2") (pintype "bidirectional"))
    )
    (net (code "15") (name "/C12") (class "Default")
      (node (ref "ANSIENTER") (pin "MX2") (pinfunction "P1_MX2") (pintype "bidirectional"))
      (node (ref "HASH") (pin "MX2") (pinfunction "P1_MX2") (pintype "bidirectional"))
      (node (ref "JP3") (pin "6") (pinfunction "6_6") (pintype "passive"))
      (node (ref "MENU") (pin "MX2") (pinfunction "P1_MX2") (pintype "bidirectional"))
      (node (ref "PLUS") (pin "MX2") (pinfunction "P1_MX2") (pintype "bidirectional"))
      (node (ref "RSHIFT0") (pin "MX2") (pinfunction "P1_MX2") (pintype "bidirectional"))
      (node (ref "RSHIFT1") (pin "MX2") (pinfunction "P1_MX2") (pintype "bidirectional"))
      (node (ref "RWIN1") (pin "MX2") (pinfunction "P1_MX2") (pintype "bidirectional"))
      (node (ref "R_BRACKET") (pin "MX2") (pinfunction "P1_MX2") (pintype "bidirectional"))
    )
    (net (code "16") (name "/C13") (class "Default")
      (node (ref "BACKSLASH") (pin "MX2") (pinfunction "P1_MX2") (pintype "bidirectional"))
      (node (ref "BACKSLASHR0") (pin "MX2") (pinfunction "P1_MX2") (pintype "bidirectional"))
      (node (ref "BACKSPACE") (pin "MX2") (pinfunction "P1_MX2") (pintype "bidirectional"))
      (node (ref "DELETE") (pin "MX2") (pinfunction "P1_MX2") (pintype "bidirectional"))
      (node (ref "ISOENTER") (pin "MX2") (pinfunction "P1_MX2") (pintype "bidirectional"))
      (node (ref "JP3") (pin "5") (pinfunction "5_5") (pintype "passive"))
      (node (ref "RCTRL0") (pin "MX2") (pinfunction "P1_MX2") (pintype "bidirectional"))
      (node (ref "RCTRL1") (pin "MX2") (pinfunction "P1_MX2") (pintype "bidirectional"))
      (node (ref "U$57") (pin "MX2") (pinfunction "P1_MX2") (pintype "bidirectional"))
    )
    (net (code "17") (name "/EN") (class "Default")
      (node (ref "JP3") (pin "2") (pinfunction "2_2") (pintype "passive"))
    )
    (net (code "18") (name "/N$76") (class "Default")
      (node (ref "JP3") (pin "4") (pinfunction "4_4") (pintype "passive"))
    )
    (net (code "19") (name "/ROW0") (class "Default")
      (node (ref "D1") (pin "C") (pinfunction "C_C") (pintype "passive"))
      (node (ref "D10") (pin "C") (pinfunction "C_C") (pintype "passive"))
      (node (ref "D11") (pin "C") (pinfunction "C_C") (pintype "passive"))
      (node (ref "D12") (pin "C") (pinfunction "C_C") (pintype "passive"))
      (node (ref "D13") (pin "C") (pinfunction "C_C") (pintype "passive"))
      (node (ref "D14") (pin "C") (pinfunction "C_C") (pintype "passive"))
      (node (ref "D2") (pin "C") (pinfunction "C_C") (pintype "passive"))
      (node (ref "D3") (pin "C") (pinfunction "C_C") (pintype "passive"))
      (node (ref "D4") (pin "C") (pinfunction "C_C") (pintype "passive"))
      (node (ref "D5") (pin "C") (pinfunction "C_C") (pintype "passive"))
      (node (ref "D6") (pin "C") (pinfunction "C_C") (pintype "passive"))
      (node (ref "D7") (pin "C") (pinfunction "C_C") (pintype "passive"))
      (node (ref "D8") (pin "C") (pinfunction "C_C") (pintype "passive"))
      (node (ref "D9") (pin "C") (pinfunction "C_C") (pintype "passive"))
      (node (ref "JP1") (pin "4") (pinfunction "4_4") (pintype "passive"))
    )
    (net (code "20") (name "/ROW1") (class "Default")
      (node (ref "D15") (pin "C") (pinfunction "C_C") (pintype "passive"))
      (node (ref "D16") (pin "C") (pinfunction "C_C") (pintype "passive"))
      (node (ref "D17") (pin "C") (pinfunction "C_C") (pintype "passive"))
      (node (ref "D18") (pin "C") (pinfunction "C_C") (pintype "passive"))
      (node (ref "D19") (pin "C") (pinfunction "C_C") (pintype "passive"))
      (node (ref "D20") (pin "C") (pinfunction "C_C") (pintype "passive"))
      (node (ref "D21") (pin "C") (pinfunction "C_C") (pintype "passive"))
      (node (ref "D22") (pin "C") (pinfunction "C_C") (pintype "passive"))
      (node (ref "D23") (pin "C") (pinfunction "C_C") (pintype "passive"))
      (node (ref "D24") (pin "C") (pinfunction "C_C") (pintype "passive"))
      (node (ref "D25") (pin "C") (pinfunction "C_C") (pintype "passive"))
      (node (ref "D26") (pin "C") (pinfunction "C_C") (pintype "passive"))
      (node (ref "D27") (pin "C") (pinfunction "C_C") (pintype "passive"))
      (node (ref "D28") (pin "C") (pinfunction "C_C") (pintype "passive"))
      (node (ref "JP1") (pin "3") (pinfunction "3_3") (pintype "passive"))
    )
    (net (code "21") (name "/ROW2") (class "Default")
      (node (ref "D43") (pin "C") (pinfunction "C_C") (pintype "passive"))
      (node (ref "D44") (pin "C") (pinfunction "C_C") (pintype "passive"))
      (node (ref "D45") (pin "C") (pinfunction "C_C") (pintype "passive"))
      (node (ref "D46") (pin "C") (pinfunction "C_C") (pintype "passive"))
      (node (ref "D47") (pin "C") (pinfunction "C_C") (pintype "passive"))
      (node (ref "D48") (pin "C") (pinfunction "C_C") (pintype "passive"))
      (node (ref "D57") (pin "C") (pinfunction "C_C") (pintype "passive"))
      (node (ref "D58") (pin "C") (pinfunction "C_C") (pintype "passive"))
      (node (ref "D59") (pin "C") (pinfunction "C_C") (pintype "passive"))
      (node (ref "D60") (pin "C") (pinfunction "C_C") (pintype "passive"))
      (node (ref "D61") (pin "C") (pinfunction "C_C") (pintype "passive"))
      (node (ref "D62") (pin "C") (pinfunction "C_C") (pintype "passive"))
      (node (ref "D63") (pin "C") (pinfunction "C_C") (pintype "passive"))
      (node (ref "D64") (pin "C") (pinfunction "C_C") (pintype "passive"))
      (node (ref "JP1") (pin "2") (pinfunction "2_2") (pintype "passive"))
    )
    (net (code "22") (name "/ROW3") (class "Default")
      (node (ref "D29") (pin "C") (pinfunction "C_C") (pintype "passive"))
      (node (ref "D30") (pin "C") (pinfunction "C_C") (pintype "passive"))
      (node (ref "D31") (pin "C") (pinfunction "C_C") (pintype "passive"))
      (node (ref "D32") (pin "C") (pinfunction "C_C") (pintype "passive"))
      (node (ref "D33") (pin "C") (pinfunction "C_C") (pintype "passive"))
      (node (ref "D34") (pin "C") (pinfunction "C_C") (pintype "passive"))
      (node (ref "D35") (pin "C") (pinfunction "C_C") (pintype "passive"))
      (node (ref "D36") (pin "C") (pinfunction "C_C") (pintype "passive"))
      (node (ref "D37") (pin "C") (pinfunction "C_C") (pintype "passive"))
      (node (ref "D38") (pin "C") (pinfunction "C_C") (pintype "passive"))
      (node (ref "D39") (pin "C") (pinfunction "C_C") (pintype "passive"))
      (node (ref "D40") (pin "C") (pinfunction "C_C") (pintype "passive"))
      (node (ref "D41") (pin "C") (pinfunction "C_C") (pintype "passive"))
      (node (ref "D42") (pin "C") (pinfunction "C_C") (pintype "passive"))
      (node (ref "JP1") (pin "1") (pinfunction "1_1") (pintype "passive"))
    )
    (net (code "23") (name "/ROW4") (class "Default")
      (node (ref "D49") (pin "C") (pinfunction "C_C") (pintype "passive"))
      (node (ref "D50") (pin "C") (pinfunction "C_C") (pintype "passive"))
      (node (ref "D51") (pin "C") (pinfunction "C_C") (pintype "passive"))
      (node (ref "D52") (pin "C") (pinfunction "C_C") (pintype "passive"))
      (node (ref "D53") (pin "C") (pinfunction "C_C") (pintype "passive"))
      (node (ref "D54") (pin "C") (pinfunction "C_C") (pintype "passive"))
      (node (ref "D55") (pin "C") (pinfunction "C_C") (pintype "passive"))
      (node (ref "D56") (pin "C") (pinfunction "C_C") (pintype "passive"))
      (node (ref "JP3") (pin "11") (pinfunction "11_11") (pintype "passive"))
    )
    (net (code "24") (name "/SDA") (class "Default")
      (node (ref "JP3") (pin "12") (pinfunction "12_12") (pintype "passive"))
    )
    (net (code "25") (name "/~{RESET}") (class "Default")
      (node (ref "JP1") (pin "16") (pinfunction "16_16") (pintype "passive"))
    )
    (net (code "26") (name "GND") (class "Default")
      (node (ref "JP1") (pin "13") (pinfunction "13_13") (pintype "passive"))
      (node (ref "X1") (pin "1") (pinfunction "1_1") (pintype "passive"))
      (node (ref "X2") (pin "1") (pinfunction "1_1") (pintype "passive"))
      (node (ref "X3") (pin "1") (pinfunction "1_1") (pintype "passive"))
      (node (ref "X4") (pin "1") (pinfunction "1_1") (pintype "passive"))
    )
    (net (code "27") (name "Net-(A-P0)") (class "Default")
      (node (ref "A") (pin "MX1") (pinfunction "P0_MX1") (pintype "bidirectional"))
      (node (ref "D44") (pin "A") (pinfunction "A_A") (pintype "passive"))
    )
    (net (code "28") (name "Net-(ANSIENTER-P0)") (class "Default")
      (node (ref "ANSIENTER") (pin "MX1") (pinfunction "P0_MX1") (pintype "bidirectional"))
      (node (ref "D63") (pin "A") (pinfunction "A_A") (pintype "passive"))
      (node (ref "HASH") (pin "MX1") (pinfunction "P0_MX1") (pintype "bidirectional"))
    )
    (net (code "29") (name "Net-(APOSTROPHE-P0)") (class "Default")
      (node (ref "APOSTROPHE") (pin "MX1") (pinfunction "P0_MX1") (pintype "bidirectional"))
      (node (ref "D62") (pin "A") (pinfunction "A_A") (pintype "passive"))
    )
    (net (code "30") (name "Net-(B-P0)") (class "Default")
      (node (ref "B") (pin "MX1") (pinfunction "P0_MX1") (pintype "bidirectional"))
      (node (ref "D35") (pin "A") (pinfunction "A_A") (pintype "passive"))
    )
    (net (code "31") (name "Net-(BACKSLASH-P0)") (class "Default")
      (node (ref "BACKSLASH") (pin "MX1") (pinfunction "P0_MX1") (pintype "bidirectional"))
      (node (ref "D28") (pin "A") (pinfunction "A_A") (pintype "passive"))
      (node (ref "ISOENTER") (pin "MX1") (pinfunction "P0_MX1") (pintype "bidirectional"))
    )
    (net (code "32") (name "Net-(BACKSLASHR0-P0)") (class "Default")
      (node (ref "BACKSLASHR0") (pin "MX1") (pinfunction "P0_MX1") (pintype "bidirectional"))
      (node (ref "BACKSPACE") (pin "MX1") (pinfunction "P0_MX1") (pintype "bidirectional"))
      (node (ref "D14") (pin "A") (pinfunction "A_A") (pintype "passive"))
    )
    (net (code "33") (name "Net-(BACKSLASHR3-P0)") (class "Default")
      (node (ref "BACKSLASHR3") (pin "MX1") (pinfunction "P0_MX1") (pintype "bidirectional"))
      (node (ref "D30") (pin "A") (pinfunction "A_A") (pintype "passive"))
    )
    (net (code "34") (name "Net-(C-P0)") (class "Default")
      (node (ref "C") (pin "MX1") (pinfunction "P0_MX1") (pintype "bidirectional"))
      (node (ref "D33") (pin "A") (pinfunction "A_A") (pintype "passive"))
    )
    (net (code "35") (name "Net-(COMMA-P0)") (class "Default")
      (node (ref "COMMA") (pin "MX1") (pinfunction "P0_MX1") (pintype "bidirectional"))
      (node (ref "D38") (pin "A") (pinfunction "A_A") (pintype "passive"))
    )
    (net (code "36") (name "Net-(D-P0)") (class "Default")
      (node (ref "D") (pin "MX1") (pinfunction "P0_MX1") (pintype "bidirectional"))
      (node (ref "D46") (pin "A") (pinfunction "A_A") (pintype "passive"))
    )
    (net (code "37") (name "Net-(DELETE-P0)") (class "Default")
      (node (ref "D64") (pin "A") (pinfunction "A_A") (pintype "passive"))
      (node (ref "DELETE") (pin "MX1") (pinfunction "P0_MX1") (pintype "bidirectional"))
    )
    (net (code "38") (name "Net-(E-P0)") (class "Default")
      (node (ref "D18") (pin "A") (pinfunction "A_A") (pintype "passive"))
      (node (ref "E") (pin "MX1") (pinfunction "P0_MX1") (pintype "bidirectional"))
    )
    (net (code "39") (name "Net-(EIGHT-P0)") (class "Default")
      (node (ref "D9") (pin "A") (pinfunction "A_A") (pintype "passive"))
      (node (ref "EIGHT") (pin "MX1") (pinfunction "P0_MX1") (pintype "bidirectional"))
    )
    (net (code "40") (name "Net-(ESC-P0)") (class "Default")
      (node (ref "D1") (pin "A") (pinfunction "A_A") (pintype "passive"))
      (node (ref "ESC") (pin "MX1") (pinfunction "P0_MX1") (pintype "bidirectional"))
    )
    (net (code "41") (name "Net-(F-P0)") (class "Default")
      (node (ref "D47") (pin "A") (pinfunction "A_A") (pintype "passive"))
      (node (ref "F") (pin "MX1") (pinfunction "P0_MX1") (pintype "bidirectional"))
    )
    (net (code "42") (name "Net-(FIVE-P0)") (class "Default")
      (node (ref "D6") (pin "A") (pinfunction "A_A") (pintype "passive"))
      (node (ref "FIVE") (pin "MX1") (pinfunction "P0_MX1") (pintype "bidirectional"))
    )
    (net (code "43") (name "Net-(FORWARDSLASH-P0)") (class "Default")
      (node (ref "D40") (pin "A") (pinfunction "A_A") (pintype "passive"))
      (node (ref "FORWARDSLASH") (pin "MX1") (pinfunction "P0_MX1") (pintype "bidirectional"))
    )
    (net (code "44") (name "Net-(FOUR-P0)") (class "Default")
      (node (ref "D5") (pin "A") (pinfunction "A_A") (pintype "passive"))
      (node (ref "FOUR") (pin "MX1") (pinfunction "P0_MX1") (pintype "bidirectional"))
    )
    (net (code "45") (name "Net-(G-P0)") (class "Default")
      (node (ref "D48") (pin "A") (pinfunction "A_A") (pintype "passive"))
      (node (ref "G") (pin "MX1") (pinfunction "P0_MX1") (pintype "bidirectional"))
    )
    (net (code "46") (name "Net-(H-P0)") (class "Default")
      (node (ref "D57") (pin "A") (pinfunction "A_A") (pintype "passive"))
      (node (ref "H") (pin "MX1") (pinfunction "P0_MX1") (pintype "bidirectional"))
    )
    (net (code "47") (name "Net-(I-P0)") (class "Default")
      (node (ref "D23") (pin "A") (pinfunction "A_A") (pintype "passive"))
      (node (ref "I") (pin "MX1") (pinfunction "P0_MX1") (pintype "bidirectional"))
    )
    (net (code "48") (name "Net-(J-P0)") (class "Default")
      (node (ref "D58") (pin "A") (pinfunction "A_A") (pintype "passive"))
      (node (ref "J") (pin "MX1") (pinfunction "P0_MX1") (pintype "bidirectional"))
    )
    (net (code "49") (name "Net-(K-P0)") (class "Default")
      (node (ref "D59") (pin "A") (pinfunction "A_A") (pintype "passive"))
      (node (ref "K") (pin "MX1") (pinfunction "P0_MX1") (pintype "bidirectional"))
    )
    (net (code "50") (name "Net-(L-P0)") (class "Default")
      (node (ref "D60") (pin "A") (pinfunction "A_A") (pintype "passive"))
      (node (ref "L") (pin "MX1") (pinfunction "P0_MX1") (pintype "bidirectional"))
    )
    (net (code "51") (name "Net-(LALT0-P0)") (class "Default")
      (node (ref "D51") (pin "A") (pinfunction "A_A") (pintype "passive"))
      (node (ref "LALT0") (pin "MX1") (pinfunction "P0_MX1") (pintype "bidirectional"))
      (node (ref "LALT1") (pin "MX1") (pinfunction "P0_MX1") (pintype "bidirectional"))
    )
    (net (code "52") (name "Net-(LCTRL0-P0)") (class "Default")
      (node (ref "D49") (pin "A") (pinfunction "A_A") (pintype "passive"))
      (node (ref "LCTRL0") (pin "MX1") (pinfunction "P0_MX1") (pintype "bidirectional"))
      (node (ref "LCTRL1") (pin "MX1") (pinfunction "P0_MX1") (pintype "bidirectional"))
    )
    (net (code "53") (name "Net-(LGUI1-P0)") (class "Default")
      (node (ref "D50") (pin "A") (pinfunction "A_A") (pintype "passive"))
      (node (ref "LGUI1") (pin "MX1") (pinfunction "P0_MX1") (pintype "bidirectional"))
      (node (ref "LWIN0") (pin "MX1") (pinfunction "P0_MX1") (pintype "bidirectional"))
    )
    (net (code "54") (name "Net-(L_BRACKET-P0)") (class "Default")
      (node (ref "D26") (pin "A") (pinfunction "A_A") (pintype "passive"))
      (node (ref "L_BRACKET") (pin "MX1") (pinfunction "P0_MX1") (pintype "bidirectional"))
    )
    (net (code "55") (name "Net-(M-P0)") (class "Default")
      (node (ref "D37") (pin "A") (pinfunction "A_A") (pintype "passive"))
      (node (ref "M") (pin "MX1") (pinfunction "P0_MX1") (pintype "bidirectional"))
    )
    (net (code "56") (name "Net-(MENU-P0)") (class "Default")
      (node (ref "D54") (pin "A") (pinfunction "A_A") (pintype "passive"))
      (node (ref "MENU") (pin "MX1") (pinfunction "P0_MX1") (pintype "bidirectional"))
      (node (ref "RWIN1") (pin "MX1") (pinfunction "P0_MX1") (pintype "bidirectional"))
    )
    (net (code "57") (name "Net-(MINUS-P0)") (class "Default")
      (node (ref "D12") (pin "A") (pinfunction "A_A") (pintype "passive"))
      (node (ref "MINUS") (pin "MX1") (pinfunction "P0_MX1") (pintype "bidirectional"))
    )
    (net (code "58") (name "Net-(N-P0)") (class "Default")
      (node (ref "D36") (pin "A") (pinfunction "A_A") (pintype "passive"))
      (node (ref "N") (pin "MX1") (pinfunction "P0_MX1") (pintype "bidirectional"))
    )
    (net (code "59") (name "Net-(NINE-P0)") (class "Default")
      (node (ref "D10") (pin "A") (pinfunction "A_A") (pintype "passive"))
      (node (ref "NINE") (pin "MX1") (pinfunction "P0_MX1") (pintype "bidirectional"))
    )
    (net (code "60") (name "Net-(O-P0)") (class "Default")
      (node (ref "D24") (pin "A") (pinfunction "A_A") (pintype "passive"))
      (node (ref "O") (pin "MX1") (pinfunction "P0_MX1") (pintype "bidirectional"))
    )
    (net (code "61") (name "Net-(ONE-P0)") (class "Default")
      (node (ref "D2") (pin "A") (pinfunction "A_A") (pintype "passive"))
      (node (ref "ONE") (pin "MX1") (pinfunction "P0_MX1") (pintype "bidirectional"))
    )
    (net (code "62") (name "Net-(P-P0)") (class "Default")
      (node (ref "D25") (pin "A") (pinfunction "A_A") (pintype "passive"))
      (node (ref "P") (pin "MX1") (pinfunction "P0_MX1") (pintype "bidirectional"))
    )
    (net (code "63") (name "Net-(PERIOD-P0)") (class "Default")
      (node (ref "D39") (pin "A") (pinfunction "A_A") (pintype "passive"))
      (node (ref "PERIOD") (pin "MX1") (pinfunction "P0_MX1") (pintype "bidirectional"))
    )
    (net (code "64") (name "Net-(PLUS-P0)") (class "Default")
      (node (ref "D13") (pin "A") (pinfunction "A_A") (pintype "passive"))
      (node (ref "PLUS") (pin "MX1") (pinfunction "P0_MX1") (pintype "bidirectional"))
    )
    (net (code "65") (name "Net-(Q-P0)") (class "Default")
      (node (ref "D16") (pin "A") (pinfunction "A_A") (pintype "passive"))
      (node (ref "Q") (pin "MX1") (pinfunction "P0_MX1") (pintype "bidirectional"))
    )
    (net (code "66") (name "Net-(R-P0)") (class "Default")
      (node (ref "D19") (pin "A") (pinfunction "A_A") (pintype "passive"))
      (node (ref "R") (pin "MX1") (pinfunction "P0_MX1") (pintype "bidirectional"))
    )
    (net (code "67") (name "Net-(RALT0-P0)") (class "Default")
      (node (ref "D52") (pin "A") (pinfunction "A_A") (pintype "passive"))
      (node (ref "RALT0") (pin "MX1") (pinfunction "P0_MX1") (pintype "bidirectional"))
    )
    (net (code "68") (name "Net-(RALT1-P0)") (class "Default")
      (node (ref "D53") (pin "A") (pinfunction "A_A") (pintype "passive"))
      (node (ref "RALT1") (pin "MX1") (pinfunction "P0_MX1") (pintype "bidirectional"))
      (node (ref "RWIN0") (pin "MX1") (pinfunction "P0_MX1") (pintype "bidirectional"))
    )
    (net (code "69") (name "Net-(RCTRL0-P0)") (class "Default")
      (node (ref "D56") (pin "A") (pinfunction "A_A") (pintype "passive"))
      (node (ref "RCTRL0") (pin "MX1") (pinfunction "P0_MX1") (pintype "bidirectional"))
      (node (ref "RCTRL1") (pin "MX1") (pinfunction "P0_MX1") (pintype "bidirectional"))
    )
    (net (code "70") (name "Net-(RSHIFT0-P0)") (class "Default")
      (node (ref "D41") (pin "A") (pinfunction "A_A") (pintype "passive"))
      (node (ref "RSHIFT0") (pin "MX1") (pinfunction "P0_MX1") (pintype "bidirectional"))
      (node (ref "RSHIFT1") (pin "MX1") (pinfunction "P0_MX1") (pintype "bidirectional"))
    )
    (net (code "71") (name "Net-(R_BRACKET-P0)") (class "Default")
      (node (ref "D27") (pin "A") (pinfunction "A_A") (pintype "passive"))
      (node (ref "R_BRACKET") (pin "MX1") (pinfunction "P0_MX1") (pintype "bidirectional"))
    )
    (net (code "72") (name "Net-(S-P0)") (class "Default")
      (node (ref "D45") (pin "A") (pinfunction "A_A") (pintype "passive"))
      (node (ref "S") (pin "MX1") (pinfunction "P0_MX1") (pintype "bidirectional"))
    )
    (net (code "73") (name "Net-(SEMICOLON-P0)") (class "Default")
      (node (ref "D61") (pin "A") (pinfunction "A_A") (pintype "passive"))
      (node (ref "SEMICOLON") (pin "MX1") (pinfunction "P0_MX1") (pintype "bidirectional"))
    )
    (net (code "74") (name "Net-(SEVEN-P0)") (class "Default")
      (node (ref "D8") (pin "A") (pinfunction "A_A") (pintype "passive"))
      (node (ref "SEVEN") (pin "MX1") (pinfunction "P0_MX1") (pintype "bidirectional"))
    )
    (net (code "75") (name "Net-(SHIFT0-P0)") (class "Default")
      (node (ref "D29") (pin "A") (pinfunction "A_A") (pintype "passive"))
      (node (ref "SHIFT0") (pin "MX1") (pinfunction "P0_MX1") (pintype "bidirectional"))
      (node (ref "SHIFT1") (pin "MX1") (pinfunction "P0_MX1") (pintype "bidirectional"))
    )
    (net (code "76") (name "Net-(SIX-P0)") (class "Default")
      (node (ref "D7") (pin "A") (pinfunction "A_A") (pintype "passive"))
      (node (ref "SIX") (pin "MX1") (pinfunction "P0_MX1") (pintype "bidirectional"))
    )
    (net (code "77") (name "Net-(SPACE0-P0)") (class "Default")
      (node (ref "D55") (pin "A") (pinfunction "A_A") (pintype "passive"))
      (node (ref "SPACE0") (pin "MX1") (pinfunction "P0_MX1") (pintype "bidirectional"))
      (node (ref "SPACE1") (pin "MX1") (pinfunction "P0_MX1") (pintype "bidirectional"))
    )
    (net (code "78") (name "Net-(STEPPED-P0)") (class "Default")
      (node (ref "D43") (pin "A") (pinfunction "A_A") (pintype "passive"))
      (node (ref "STEPPED") (pin "MX1") (pinfunction "P0_MX1") (pintype "bidirectional"))
      (node (ref "USELESS") (pin "MX1") (pinfunction "P0_MX1") (pintype "bidirectional"))
    )
    (net (code "79") (name "Net-(T-P0)") (class "Default")
      (node (ref "D20") (pin "A") (pinfunction "A_A") (pintype "passive"))
      (node (ref "T") (pin "MX1") (pinfunction "P0_MX1") (pintype "bidirectional"))
    )
    (net (code "80") (name "Net-(TAB-P0)") (class "Default")
      (node (ref "D15") (pin "A") (pinfunction "A_A") (pintype "passive"))
      (node (ref "TAB") (pin "MX1") (pinfunction "P0_MX1") (pintype "bidirectional"))
    )
    (net (code "81") (name "Net-(THREE-P0)") (class "Default")
      (node (ref "D4") (pin "A") (pinfunction "A_A") (pintype "passive"))
      (node (ref "THREE") (pin "MX1") (pinfunction "P0_MX1") (pintype "bidirectional"))
    )
    (net (code "82") (name "Net-(TWO-P0)") (class "Default")
      (node (ref "D3") (pin "A") (pinfunction "A_A") (pintype "passive"))
      (node (ref "TWO") (pin "MX1") (pinfunction "P0_MX1") (pintype "bidirectional"))
    )
    (net (code "83") (name "Net-(U$57-P0)") (class "Default")
      (node (ref "D42") (pin "A") (pinfunction "A_A") (pintype "passive"))
      (node (ref "U$57") (pin "MX1") (pinfunction "P0_MX1") (pintype "bidirectional"))
    )
    (net (code "84") (name "Net-(U-P0)") (class "Default")
      (node (ref "D22") (pin "A") (pinfunction "A_A") (pintype "passive"))
      (node (ref "U") (pin "MX1") (pinfunction "P0_MX1") (pintype "bidirectional"))
    )
    (net (code "85") (name "Net-(V-P0)") (class "Default")
      (node (ref "D34") (pin "A") (pinfunction "A_A") (pintype "passive"))
      (node (ref "V") (pin "MX1") (pinfunction "P0_MX1") (pintype "bidirectional"))
    )
    (net (code "86") (name "Net-(W-P0)") (class "Default")
      (node (ref "D17") (pin "A") (pinfunction "A_A") (pintype "passive"))
      (node (ref "W") (pin "MX1") (pinfunction "P0_MX1") (pintype "bidirectional"))
    )
    (net (code "87") (name "Net-(X-P0)") (class "Default")
      (node (ref "D32") (pin "A") (pinfunction "A_A") (pintype "passive"))
      (node (ref "X") (pin "MX1") (pinfunction "P0_MX1") (pintype "bidirectional"))
    )
    (net (code "88") (name "Net-(Y-P0)") (class "Default")
      (node (ref "D21") (pin "A") (pinfunction "A_A") (pintype "passive"))
      (node (ref "Y") (pin "MX1") (pinfunction "P0_MX1") (pintype "bidirectional"))
    )
    (net (code "89") (name "Net-(Z-P0)") (class "Default")
      (node (ref "D31") (pin "A") (pinfunction "A_A") (pintype "passive"))
      (node (ref "Z") (pin "MX1") (pinfunction "P0_MX1") (pintype "bidirectional"))
    )
    (net (code "90") (name "Net-(ZERO-P0)") (class "Default")
      (node (ref "D11") (pin "A") (pinfunction "A_A") (pintype "passive"))
      (node (ref "ZERO") (pin "MX1") (pinfunction "P0_MX1") (pintype "bidirectional"))
    )
    (net (code "91") (name "VBAT") (class "Default")
      (node (ref "JP3") (pin "1") (pinfunction "1_1") (pintype "passive"))
      (node (ref "X1") (pin "2") (pinfunction "2_2") (pintype "passive"))
      (node (ref "X2") (pin "2") (pinfunction "2_2") (pintype "passive"))
      (node (ref "X3") (pin "2") (pinfunction "2_2") (pintype "passive"))
      (node (ref "X4") (pin "2") (pinfunction "2_2") (pintype "passive"))
    )
    (net (code "92") (name "VBUS") (class "Default")
      (node (ref "JP3") (pin "3") (pinfunction "3_3") (pintype "passive"))
    )
  )
)
